# Sound_Recorder_IoT_updated.net
KiCad netlist of a schematic drawn in EasyEDA Pro
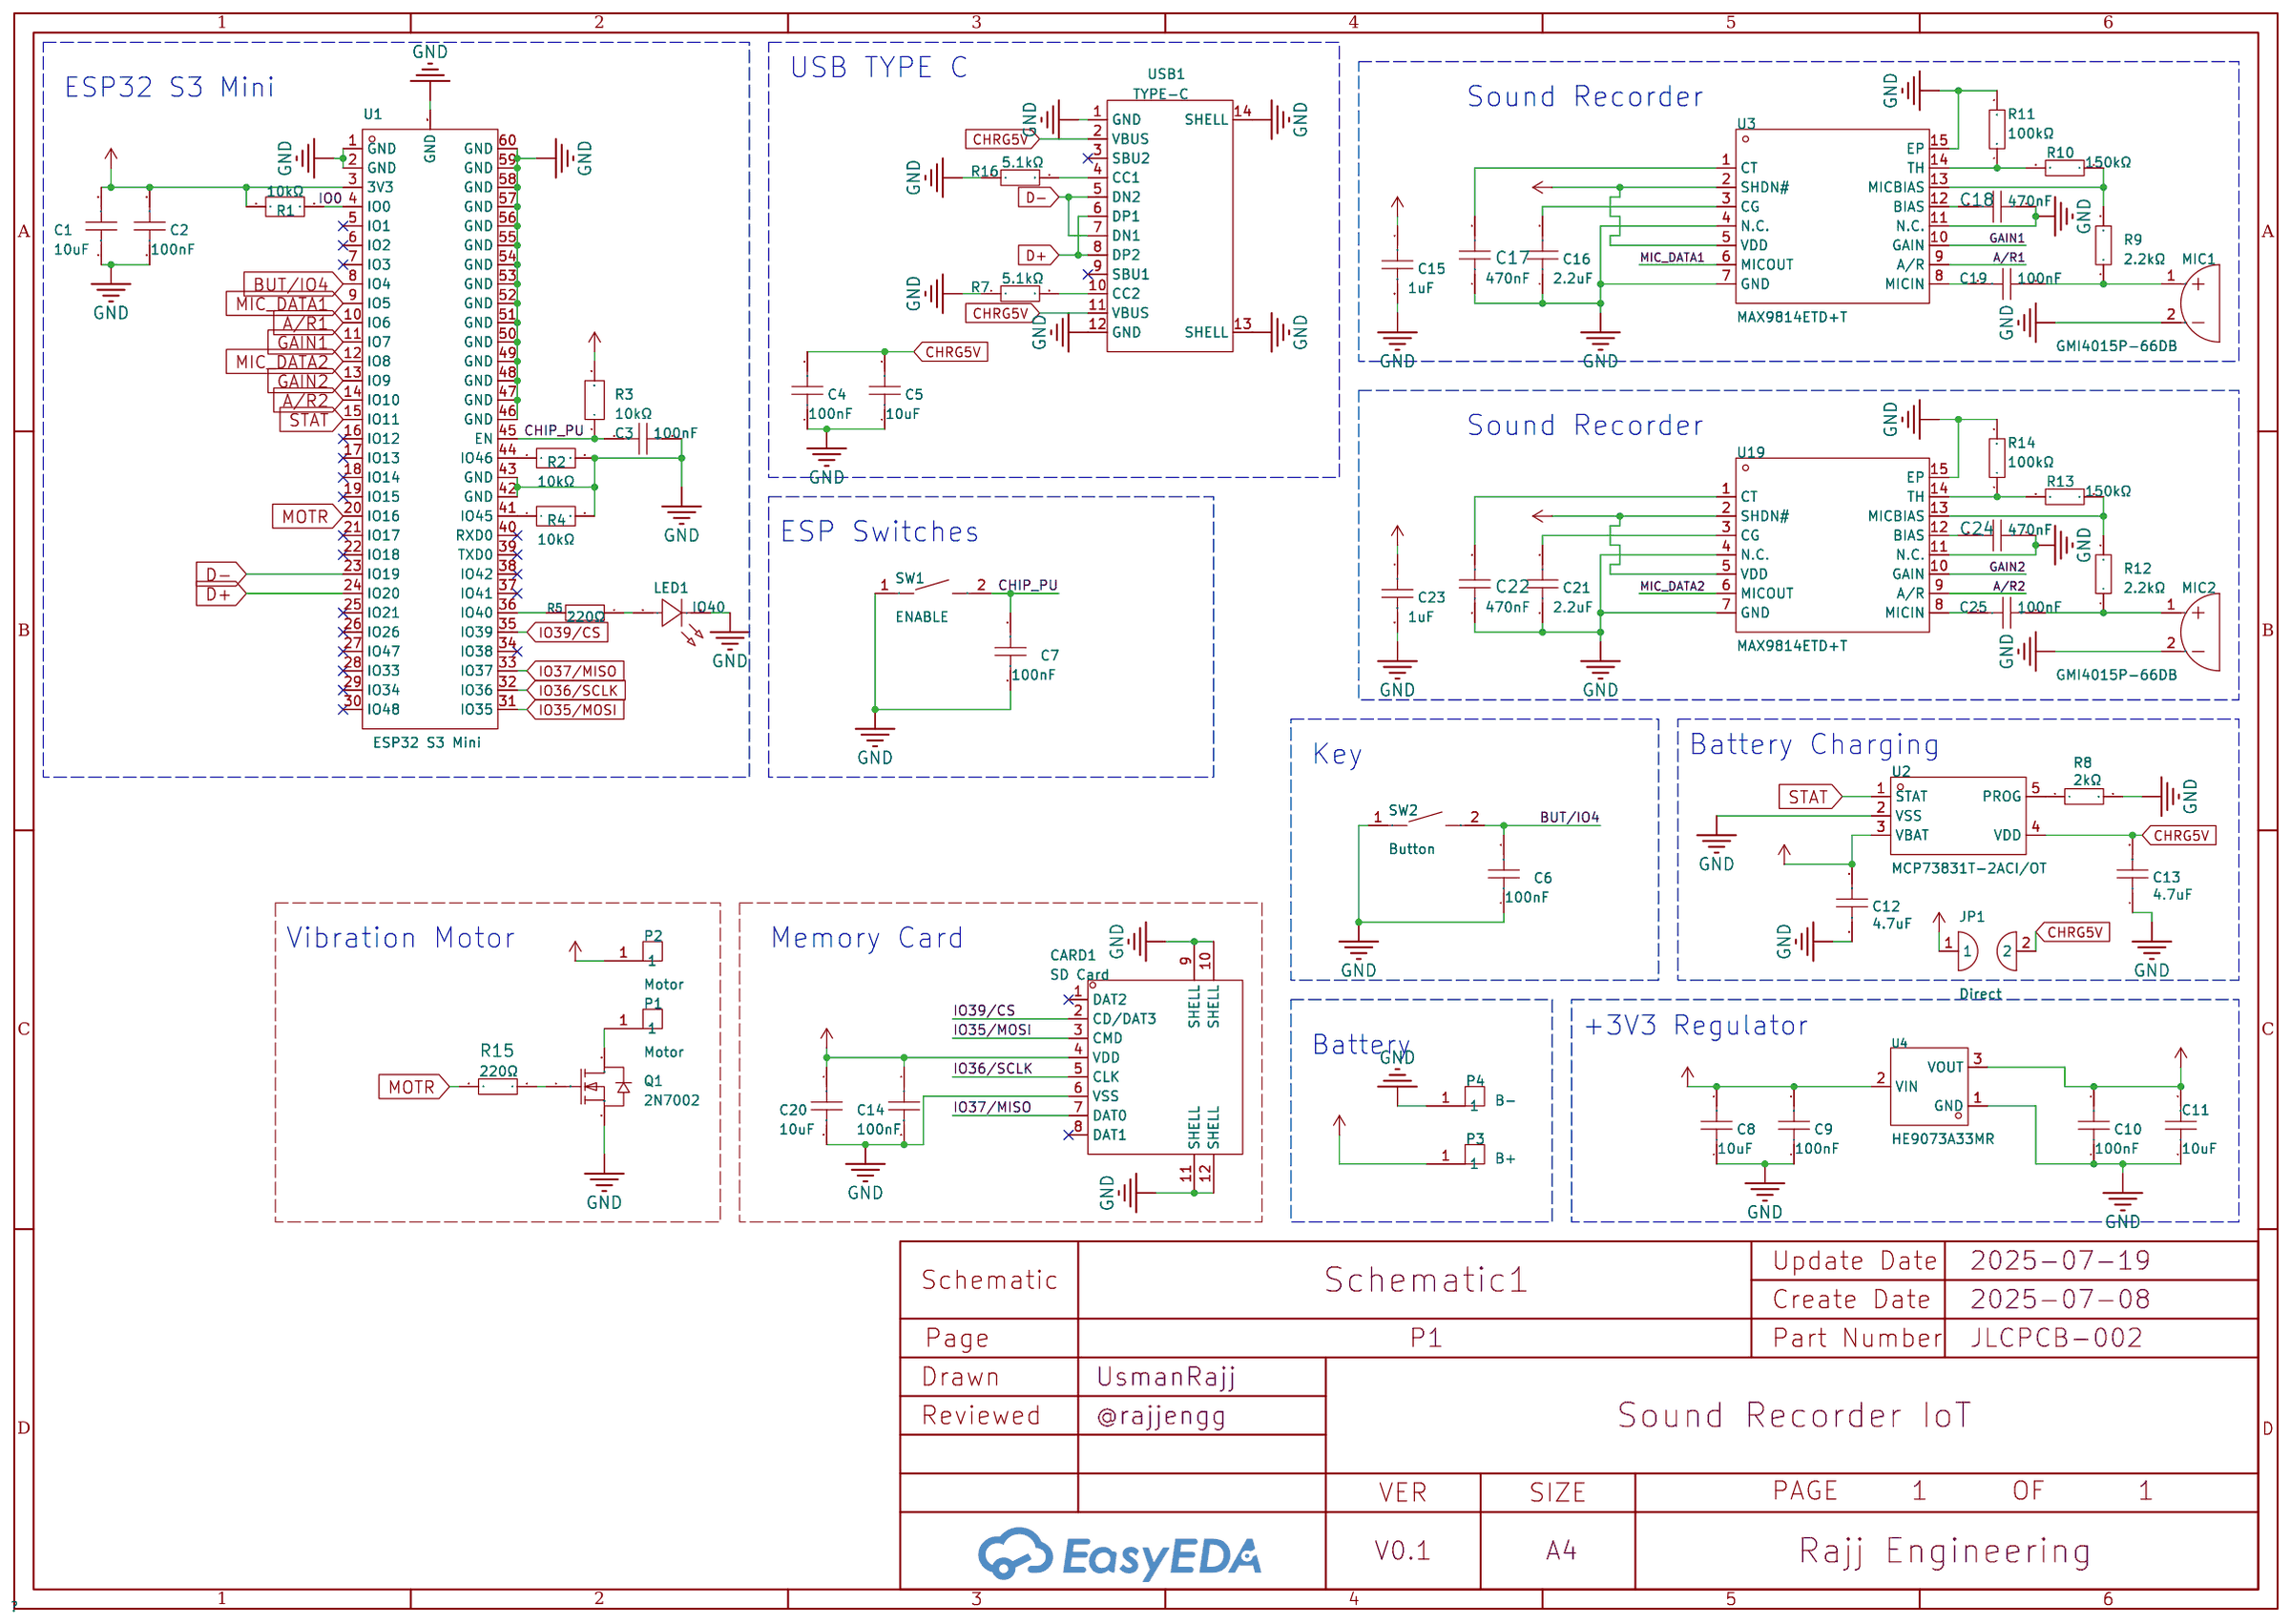
[diagram p0: schematic sheet]

(export (version "E")
  (design (tool "Eeschema 10.0.6"))
  (components
    (comp (ref "C1")
      (value "10uF")
      (footprint "easyedapro:C0402")
      (fields
        (field (name "Manufacturer Part") "CL05A106MP5NUNC")
        (field (name "Manufacturer") "SAMSUNG(三星)")
      )
      (libsource (lib "easyedapro") (part "CL05A106MP5NUNC_C315248"))
    )
    (comp (ref "C2")
      (value "100nF")
      (footprint "easyedapro:C0201")
      (description "Capacitance:100nF Tolerance:±10% Tolerance:±10% Voltage Rating:10V Temperature Coefficient:X5R")
      (fields (field (name "Manufacturer Part") "0201X104K100NT") (field (name "Manufacturer") "FH(风华)"))
      (libsource (lib "easyedapro") (part "0201X104K100NT"))
    )
    (comp (ref "C3")
      (value "100nF")
      (footprint "easyedapro:C0201")
      (description "Capacitance:100nF Tolerance:±10% Tolerance:±10% Voltage Rating:10V Temperature Coefficient:X5R")
      (fields (field (name "Manufacturer Part") "0201X104K100NT") (field (name "Manufacturer") "FH(风华)"))
      (libsource (lib "easyedapro") (part "0201X104K100NT"))
    )
    (comp (ref "C4")
      (value "100nF")
      (footprint "easyedapro:C0201")
      (description "Capacitance:100nF Tolerance:±10% Tolerance:±10% Voltage Rating:10V Temperature Coefficient:X5R")
      (fields (field (name "Manufacturer Part") "0201X104K100NT") (field (name "Manufacturer") "FH(风华)"))
      (libsource (lib "easyedapro") (part "0201X104K100NT"))
    )
    (comp (ref "C5")
      (value "10uF")
      (footprint "easyedapro:C0402")
      (fields
        (field (name "Manufacturer Part") "CL05A106MP5NUNC")
        (field (name "Manufacturer") "SAMSUNG(三星)")
      )
      (libsource (lib "easyedapro") (part "CL05A106MP5NUNC_C315248"))
    )
    (comp (ref "C6")
      (value "100nF")
      (footprint "easyedapro:C0201")
      (description "Capacitance:100nF Tolerance:±10% Tolerance:±10% Voltage Rating:10V Temperature Coefficient:X5R")
      (fields (field (name "Manufacturer Part") "0201X104K100NT") (field (name "Manufacturer") "FH(风华)"))
      (libsource (lib "easyedapro") (part "0201X104K100NT"))
    )
    (comp (ref "C7")
      (value "100nF")
      (footprint "easyedapro:C0201")
      (description "Capacitance:100nF Tolerance:±10% Tolerance:±10% Voltage Rating:10V Temperature Coefficient:X5R")
      (fields (field (name "Manufacturer Part") "0201X104K100NT") (field (name "Manufacturer") "FH(风华)"))
      (libsource (lib "easyedapro") (part "0201X104K100NT"))
    )
    (comp (ref "C8")
      (value "10uF")
      (footprint "easyedapro:C0402")
      (fields
        (field (name "Manufacturer Part") "CL05A106MP5NUNC")
        (field (name "Manufacturer") "SAMSUNG(三星)")
      )
      (libsource (lib "easyedapro") (part "CL05A106MP5NUNC_C315248"))
    )
    (comp (ref "C9")
      (value "100nF")
      (footprint "easyedapro:C0201")
      (description "Capacitance:100nF Tolerance:±10% Tolerance:±10% Voltage Rating:10V Temperature Coefficient:X5R")
      (fields (field (name "Manufacturer Part") "0201X104K100NT") (field (name "Manufacturer") "FH(风华)"))
      (libsource (lib "easyedapro") (part "0201X104K100NT"))
    )
    (comp (ref "C10")
      (value "100nF")
      (footprint "easyedapro:C0201")
      (description "Capacitance:100nF Tolerance:±10% Tolerance:±10% Voltage Rating:10V Temperature Coefficient:X5R")
      (fields (field (name "Manufacturer Part") "0201X104K100NT") (field (name "Manufacturer") "FH(风华)"))
      (libsource (lib "easyedapro") (part "0201X104K100NT"))
    )
    (comp (ref "C11")
      (value "10uF")
      (footprint "easyedapro:C0402")
      (fields
        (field (name "Manufacturer Part") "CL05A106MP5NUNC")
        (field (name "Manufacturer") "SAMSUNG(三星)")
      )
      (libsource (lib "easyedapro") (part "CL05A106MP5NUNC_C315248"))
    )
    (comp (ref "C12")
      (value "4.7uF")
      (footprint "easyedapro:C0402")
      (fields
        (field (name "Manufacturer Part") "CL05A475KP5NRNC")
        (field (name "Manufacturer") "SAMSUNG(三星)")
      )
      (libsource (lib "easyedapro") (part "4.7uF"))
    )
    (comp (ref "C13")
      (value "4.7uF")
      (footprint "easyedapro:C0402")
      (fields
        (field (name "Manufacturer Part") "CL05A475KP5NRNC")
        (field (name "Manufacturer") "SAMSUNG(三星)")
      )
      (libsource (lib "easyedapro") (part "4.7uF"))
    )
    (comp (ref "C14")
      (value "100nF")
      (footprint "easyedapro:C0201")
      (description "Capacitance:100nF Tolerance:±10% Tolerance:±10% Voltage Rating:10V Temperature Coefficient:X5R")
      (fields (field (name "Manufacturer Part") "0201X104K100NT") (field (name "Manufacturer") "FH(风华)"))
      (libsource (lib "easyedapro") (part "0201X104K100NT"))
    )
    (comp (ref "C15")
      (value "1uF")
      (footprint "easyedapro:C0201")
      (fields
        (field (name "Manufacturer Part") "CL03A105MP3NSNC")
        (field (name "Manufacturer") "SAMSUNG(三星)")
      )
      (libsource (lib "easyedapro") (part "CL03A105MP3NSNC"))
    )
    (comp (ref "C16")
      (value "2.2uF")
      (footprint "easyedapro:C0201")
      (description "Capacitance:2.2uF Tolerance:±20% Tolerance:±20% Voltage Rating:6.3V Temperature Coefficient:X5R")
      (fields (field (name "Manufacturer Part") "0201X225M6R3NT") (field (name "Manufacturer") "FH(风华)"))
      (libsource (lib "easyedapro") (part "0201X225M6R3NT"))
    )
    (comp (ref "C17")
      (value "470nF")
      (footprint "easyedapro:C0201")
      (fields
        (field (name "Manufacturer Part") "GRM033R60J474KE90D")
        (field (name "Manufacturer") "muRata(村田)")
      )
      (libsource (lib "easyedapro") (part "GRM033R60J474KE90D"))
    )
    (comp (ref "C18")
      (value "470nF")
      (footprint "easyedapro:C0201")
      (fields
        (field (name "Manufacturer Part") "GRM033R60J474KE90D")
        (field (name "Manufacturer") "muRata(村田)")
      )
      (libsource (lib "easyedapro") (part "GRM033R60J474KE90D"))
    )
    (comp (ref "C19")
      (value "100nF")
      (footprint "easyedapro:C0201")
      (description "Capacitance:100nF Tolerance:±10% Tolerance:±10% Voltage Rating:10V Temperature Coefficient:X5R")
      (fields (field (name "Manufacturer Part") "0201X104K100NT") (field (name "Manufacturer") "FH(风华)"))
      (libsource (lib "easyedapro") (part "0201X104K100NT"))
    )
    (comp (ref "C20")
      (value "10uF")
      (footprint "easyedapro:C0402")
      (fields
        (field (name "Manufacturer Part") "CL05A106MP5NUNC")
        (field (name "Manufacturer") "SAMSUNG(三星)")
      )
      (libsource (lib "easyedapro") (part "CL05A106MP5NUNC_C315248"))
    )
    (comp (ref "C21")
      (value "2.2uF")
      (footprint "easyedapro:C0201")
      (description "Capacitance:2.2uF Tolerance:±20% Tolerance:±20% Voltage Rating:6.3V Temperature Coefficient:X5R")
      (fields (field (name "Manufacturer Part") "0201X225M6R3NT") (field (name "Manufacturer") "FH(风华)"))
      (libsource (lib "easyedapro") (part "0201X225M6R3NT"))
    )
    (comp (ref "C22")
      (value "470nF")
      (footprint "easyedapro:C0201")
      (fields
        (field (name "Manufacturer Part") "GRM033R60J474KE90D")
        (field (name "Manufacturer") "muRata(村田)")
      )
      (libsource (lib "easyedapro") (part "GRM033R60J474KE90D"))
    )
    (comp (ref "C23")
      (value "1uF")
      (footprint "easyedapro:C0201")
      (fields
        (field (name "Manufacturer Part") "CL03A105MP3NSNC")
        (field (name "Manufacturer") "SAMSUNG(三星)")
      )
      (libsource (lib "easyedapro") (part "CL03A105MP3NSNC"))
    )
    (comp (ref "C24")
      (value "470nF")
      (footprint "easyedapro:C0201")
      (fields
        (field (name "Manufacturer Part") "GRM033R60J474KE90D")
        (field (name "Manufacturer") "muRata(村田)")
      )
      (libsource (lib "easyedapro") (part "GRM033R60J474KE90D"))
    )
    (comp (ref "C25")
      (value "100nF")
      (footprint "easyedapro:C0201")
      (description "Capacitance:100nF Tolerance:±10% Tolerance:±10% Voltage Rating:10V Temperature Coefficient:X5R")
      (fields (field (name "Manufacturer Part") "0201X104K100NT") (field (name "Manufacturer") "FH(风华)"))
      (libsource (lib "easyedapro") (part "0201X104K100NT"))
    )
    (comp (ref "CARD1")
      (value "SD Card")
      (footprint "easyedapro:TF-SMD_TF-102-15")
      (fields (field (name "Manufacturer Part") "TF-102-15") (field (name "Manufacturer") "XUNPU(讯普)"))
      (libsource (lib "easyedapro") (part "TF-102-15"))
    )
    (comp (ref "JP1")
      (value "Direct")
      (footprint "easyedapro:jumper pad")
      (libsource (lib "easyedapro") (part "Jumper Pad"))
    )
    (comp (ref "LED1")
      (value "IO40")
      (footprint "easyedapro:LED0603-RD_BLUE")
      (fields
        (field (name "Manufacturer Part") "XL-1608UBC-04")
        (field (name "Manufacturer") "XINGLIGHT(成兴光)")
      )
      (libsource (lib "easyedapro") (part "XL-1608UBC-04"))
    )
    (comp (ref "MIC1")
      (value "GMI4015P-66DB")
      (footprint "easyedapro:MIC-TH_BD4.0-P1.4-D0.4-L-FD")
      (fields (field (name "Manufacturer") "INGHAi(赢海)"))
      (libsource (lib "easyedapro") (part "GMI4015P-66DB"))
    )
    (comp (ref "MIC2")
      (value "GMI4015P-66DB")
      (footprint "easyedapro:MIC-TH_BD4.0-P1.4-D0.4-L-FD")
      (fields (field (name "Manufacturer") "INGHAi(赢海)"))
      (libsource (lib "easyedapro") (part "GMI4015P-66DB"))
    )
    (comp (ref "P1") (value "Motor") (libsource (lib "easyedapro") (part "SMD 1.5X2 PAD")))
    (comp (ref "P2") (value "Motor") (libsource (lib "easyedapro") (part "SMD 1.5X2 PAD")))
    (comp (ref "P3") (value "B+") (libsource (lib "easyedapro") (part "SMD 1.5X2 PAD")))
    (comp (ref "P4") (value "B-") (libsource (lib "easyedapro") (part "SMD 1.5X2 PAD")))
    (comp (ref "Q1")
      (value "2N7002")
      (footprint "easyedapro:SOT-23-3_L2.9-W1.3-P1.90-LS2.4-BR")
      (fields (field (name "Manufacturer") "CJ(江苏长电/长晶)"))
      (libsource (lib "easyedapro") (part "2N7002"))
    )
    (comp (ref "R1")
      (value "10kΩ")
      (footprint "easyedapro:R0201")
      (fields
        (field (name "Manufacturer Part") "0201WMF1002TEE")
        (field (name "Manufacturer") "UNI-ROYAL(厚声)")
      )
      (libsource (lib "easyedapro") (part "0201WMF1002TEE"))
    )
    (comp (ref "R2")
      (value "10kΩ")
      (footprint "easyedapro:R0201")
      (fields
        (field (name "Manufacturer Part") "0201WMF1002TEE")
        (field (name "Manufacturer") "UNI-ROYAL(厚声)")
      )
      (libsource (lib "easyedapro") (part "0201WMF1002TEE"))
    )
    (comp (ref "R3")
      (value "10kΩ")
      (footprint "easyedapro:R0201")
      (fields
        (field (name "Manufacturer Part") "0201WMF1002TEE")
        (field (name "Manufacturer") "UNI-ROYAL(厚声)")
      )
      (libsource (lib "easyedapro") (part "0201WMF1002TEE"))
    )
    (comp (ref "R4")
      (value "10kΩ")
      (footprint "easyedapro:R0201")
      (fields
        (field (name "Manufacturer Part") "0201WMF1002TEE")
        (field (name "Manufacturer") "UNI-ROYAL(厚声)")
      )
      (libsource (lib "easyedapro") (part "0201WMF1002TEE"))
    )
    (comp (ref "R5")
      (value "220Ω")
      (footprint "easyedapro:R0402")
      (fields
        (field (name "Manufacturer Part") "0402WGF2200TCE")
        (field (name "Manufacturer") "UNI-ROYAL(厚声)")
      )
      (libsource (lib "easyedapro") (part "0402WGF2200TCE"))
    )
    (comp (ref "R7")
      (value "5.1kΩ")
      (footprint "easyedapro:R0402")
      (fields
        (field (name "Manufacturer Part") "0402WGF5101TCE")
        (field (name "Manufacturer") "UNI-ROYAL(厚声)")
      )
      (libsource (lib "easyedapro") (part "5.1kΩ"))
    )
    (comp (ref "R8")
      (value "2kΩ")
      (footprint "easyedapro:R0402")
      (fields
        (field (name "Manufacturer Part") "0402WGF2001TCE")
        (field (name "Manufacturer") "UNI-ROYAL(厚声)")
      )
      (libsource (lib "easyedapro") (part "2kΩ"))
    )
    (comp (ref "R9")
      (value "2.2kΩ")
      (footprint "easyedapro:R0201")
      (fields (field (name "Manufacturer Part") "RC0201FR-072K2L") (field (name "Manufacturer") "YAGEO(国巨)"))
      (libsource (lib "easyedapro") (part "RC0201FR-072K2L"))
    )
    (comp (ref "R10")
      (value "150kΩ")
      (footprint "easyedapro:R0201")
      (fields (field (name "Manufacturer Part") "RC0201FR-07150KL") (field (name "Manufacturer") "YAGEO(国巨)"))
      (libsource (lib "easyedapro") (part "RC0201FR-07150KL"))
    )
    (comp (ref "R11")
      (value "100kΩ")
      (footprint "easyedapro:R0201")
      (fields (field (name "Manufacturer Part") "RC0201FR-07100KL") (field (name "Manufacturer") "YAGEO(国巨)"))
      (libsource (lib "easyedapro") (part "RC0201FR-07100KL"))
    )
    (comp (ref "R12")
      (value "2.2kΩ")
      (footprint "easyedapro:R0201")
      (fields (field (name "Manufacturer Part") "RC0201FR-072K2L") (field (name "Manufacturer") "YAGEO(国巨)"))
      (libsource (lib "easyedapro") (part "RC0201FR-072K2L"))
    )
    (comp (ref "R13")
      (value "150kΩ")
      (footprint "easyedapro:R0201")
      (fields (field (name "Manufacturer Part") "RC0201FR-07150KL") (field (name "Manufacturer") "YAGEO(国巨)"))
      (libsource (lib "easyedapro") (part "RC0201FR-07150KL"))
    )
    (comp (ref "R14")
      (value "100kΩ")
      (footprint "easyedapro:R0201")
      (fields (field (name "Manufacturer Part") "RC0201FR-07100KL") (field (name "Manufacturer") "YAGEO(国巨)"))
      (libsource (lib "easyedapro") (part "RC0201FR-07100KL"))
    )
    (comp (ref "R15")
      (value "220Ω")
      (footprint "easyedapro:R0402")
      (fields
        (field (name "Manufacturer Part") "0402WGF2200TCE")
        (field (name "Manufacturer") "UNI-ROYAL(厚声)")
      )
      (libsource (lib "easyedapro") (part "0402WGF2200TCE"))
    )
    (comp (ref "R16")
      (value "5.1kΩ")
      (footprint "easyedapro:R0402")
      (fields
        (field (name "Manufacturer Part") "0402WGF5101TCE")
        (field (name "Manufacturer") "UNI-ROYAL(厚声)")
      )
      (libsource (lib "easyedapro") (part "5.1kΩ"))
    )
    (comp (ref "SW1")
      (value "ENABLE")
      (footprint "easyedapro:SW-SMD_L3.9-W3.0-P4.45")
      (fields (field (name "Manufacturer Part") "TS-1088-AR02016") (field (name "Manufacturer") "XUNPU(讯普)"))
      (libsource (lib "easyedapro") (part "TS-1088-AR02016"))
    )
    (comp (ref "SW2")
      (value "Button")
      (footprint "easyedapro:SW-SMD_L3.9-W3.0-P4.45")
      (fields (field (name "Manufacturer Part") "TS-1088-AR02016") (field (name "Manufacturer") "XUNPU(讯普)"))
      (libsource (lib "easyedapro") (part "TS-1088-AR02016"))
    )
    (comp (ref "U1")
      (value "ESP32 S3 Mini")
      (footprint "easyedapro:BULETM-SMD_ESP32-S3-MINI-1-N8")
      (fields
        (field (name "Manufacturer Part") "ESP32-S3-MINI-1-N8")
        (field (name "Manufacturer") "ESPRESSIF(乐鑫)")
      )
      (libsource (lib "easyedapro") (part "ESP32-S3-MINI-1-N8"))
    )
    (comp (ref "U2")
      (value "MCP73831T-2ACI/OT")
      (footprint "easyedapro:SOT-23-5_L3.0-W1.7-P0.95-LS2.8-BL")
      (fields (field (name "Manufacturer") "MICROCHIP(美国微芯)"))
      (libsource (lib "easyedapro") (part "MCP73831T-2ACI/OT"))
    )
    (comp (ref "U3")
      (value "MAX9814ETD+T")
      (footprint "easyedapro:TDFN-14_L3.0-W3.0-P0.40-BL-EP")
      (fields (field (name "Manufacturer") "ADI(亚德诺)/MAXIM(美信)"))
      (libsource (lib "easyedapro") (part "MAX9814ETD+T"))
    )
    (comp (ref "U4")
      (value "HE9073A33MR")
      (footprint "easyedapro:SOT-23-3_L2.9-W1.6-P1.90-LS2.8-BR-CW")
      (fields (field (name "Manufacturer") "HEERMICR(赫尔半导体)"))
      (libsource (lib "easyedapro") (part "HE9073A33MR"))
    )
    (comp (ref "U19")
      (value "MAX9814ETD+T")
      (footprint "easyedapro:TDFN-14_L3.0-W3.0-P0.40-BL-EP")
      (fields (field (name "Manufacturer") "ADI(亚德诺)/MAXIM(美信)"))
      (libsource (lib "easyedapro") (part "MAX9814ETD+T"))
    )
    (comp (ref "USB1")
      (value "TYPE-C")
      (footprint "easyedapro:USB-C-SMD_TYPE-C-6PIN-2MD-073")
      (fields
        (field (name "Manufacturer Part") "TYPE-C 16PIN 2MD(073)")
        (field (name "Manufacturer") "SHOU HAN(首韩)")
      )
      (libsource (lib "easyedapro") (part "TYPE-C"))
    )
  )
  (nets
    (net (code "1") (name "/CHIP_PU") (class "Default")
      (node (ref "C3") (pin "2") (pinfunction "2_2") (pintype "unspecified"))
      (node (ref "C7") (pin "2") (pinfunction "2_2") (pintype "unspecified"))
      (node (ref "R3") (pin "1") (pinfunction "1_1") (pintype "unspecified"))
      (node (ref "SW1") (pin "2") (pinfunction "2_2") (pintype "unspecified"))
      (node (ref "U1") (pin "45") (pinfunction "EN_45") (pintype "unspecified"))
    )
    (net (code "2") (name "/IO0") (class "Default")
      (node (ref "R1") (pin "2") (pinfunction "2_2") (pintype "unspecified"))
      (node (ref "U1") (pin "4") (pinfunction "IO0_4") (pintype "unspecified"))
    )
    (net (code "3") (name "A{slash}R1") (class "Default")
      (node (ref "U1") (pin "10") (pinfunction "IO6_10") (pintype "unspecified"))
      (node (ref "U3") (pin "9") (pinfunction "A/R_9") (pintype "unspecified"))
    )
    (net (code "4") (name "A{slash}R2") (class "Default")
      (node (ref "U1") (pin "14") (pinfunction "IO10_14") (pintype "unspecified"))
      (node (ref "U19") (pin "9") (pinfunction "A/R_9") (pintype "unspecified"))
    )
    (net (code "5") (name "BUT{slash}IO4") (class "Default")
      (node (ref "C6") (pin "2") (pinfunction "2_2") (pintype "unspecified"))
      (node (ref "SW2") (pin "2") (pinfunction "2_2") (pintype "unspecified"))
      (node (ref "U1") (pin "8") (pinfunction "IO4_8") (pintype "unspecified"))
    )
    (net (code "6") (name "CHRG5V") (class "Default")
      (node (ref "C13") (pin "2") (pinfunction "2_2") (pintype "unspecified"))
      (node (ref "C4") (pin "2") (pinfunction "2_2") (pintype "unspecified"))
      (node (ref "C5") (pin "2") (pinfunction "2_2") (pintype "unspecified"))
      (node (ref "JP1") (pin "2") (pinfunction "2_2") (pintype "input"))
      (node (ref "U2") (pin "4") (pinfunction "VDD_4") (pintype "unspecified"))
      (node (ref "USB1") (pin "11") (pinfunction "VBUS_11") (pintype "unspecified"))
      (node (ref "USB1") (pin "2") (pinfunction "VBUS_2") (pintype "unspecified"))
    )
    (net (code "7") (name "D+") (class "Default")
      (node (ref "U1") (pin "24") (pinfunction "IO20_24") (pintype "unspecified"))
      (node (ref "USB1") (pin "6") (pinfunction "DP1_6") (pintype "unspecified"))
      (node (ref "USB1") (pin "8") (pinfunction "DP2_8") (pintype "unspecified"))
    )
    (net (code "8") (name "D-") (class "Default")
      (node (ref "U1") (pin "23") (pinfunction "IO19_23") (pintype "unspecified"))
      (node (ref "USB1") (pin "5") (pinfunction "DN2_5") (pintype "unspecified"))
      (node (ref "USB1") (pin "7") (pinfunction "DN1_7") (pintype "unspecified"))
    )
    (net (code "9") (name "GAIN1") (class "Default")
      (node (ref "U1") (pin "11") (pinfunction "IO7_11") (pintype "unspecified"))
      (node (ref "U3") (pin "10") (pinfunction "GAIN_10") (pintype "unspecified"))
    )
    (net (code "10") (name "GAIN2") (class "Default")
      (node (ref "U1") (pin "13") (pinfunction "IO9_13") (pintype "unspecified"))
      (node (ref "U19") (pin "10") (pinfunction "GAIN_10") (pintype "unspecified"))
    )
    (net (code "11") (name "GND") (class "Default")
      (node (ref "C1") (pin "1") (pinfunction "1_1") (pintype "unspecified"))
      (node (ref "C10") (pin "1") (pinfunction "1_1") (pintype "unspecified"))
      (node (ref "C11") (pin "1") (pinfunction "1_1") (pintype "unspecified"))
      (node (ref "C12") (pin "1") (pinfunction "1_1") (pintype "unspecified"))
      (node (ref "C13") (pin "1") (pinfunction "1_1") (pintype "unspecified"))
      (node (ref "C14") (pin "2") (pinfunction "2_2") (pintype "unspecified"))
      (node (ref "C15") (pin "2") (pinfunction "2_2") (pintype "input"))
      (node (ref "C16") (pin "1") (pinfunction "1_1") (pintype "unspecified"))
      (node (ref "C17") (pin "1") (pinfunction "1_1") (pintype "input"))
      (node (ref "C18") (pin "1") (pinfunction "1_1") (pintype "input"))
      (node (ref "C2") (pin "1") (pinfunction "1_1") (pintype "unspecified"))
      (node (ref "C20") (pin "2") (pinfunction "2_2") (pintype "unspecified"))
      (node (ref "C21") (pin "1") (pinfunction "1_1") (pintype "unspecified"))
      (node (ref "C22") (pin "1") (pinfunction "1_1") (pintype "input"))
      (node (ref "C23") (pin "2") (pinfunction "2_2") (pintype "input"))
      (node (ref "C24") (pin "1") (pinfunction "1_1") (pintype "input"))
      (node (ref "C3") (pin "1") (pinfunction "1_1") (pintype "unspecified"))
      (node (ref "C4") (pin "1") (pinfunction "1_1") (pintype "unspecified"))
      (node (ref "C5") (pin "1") (pinfunction "1_1") (pintype "unspecified"))
      (node (ref "C6") (pin "1") (pinfunction "1_1") (pintype "unspecified"))
      (node (ref "C7") (pin "1") (pinfunction "1_1") (pintype "unspecified"))
      (node (ref "C8") (pin "1") (pinfunction "1_1") (pintype "unspecified"))
      (node (ref "C9") (pin "1") (pinfunction "1_1") (pintype "unspecified"))
      (node (ref "CARD1") (pin "10") (pinfunction "SHELL_10") (pintype "unspecified"))
      (node (ref "CARD1") (pin "11") (pinfunction "SHELL_11") (pintype "unspecified"))
      (node (ref "CARD1") (pin "12") (pinfunction "SHELL_12") (pintype "unspecified"))
      (node (ref "CARD1") (pin "6") (pinfunction "VSS_6") (pintype "unspecified"))
      (node (ref "CARD1") (pin "9") (pinfunction "SHELL_9") (pintype "unspecified"))
      (node (ref "LED1") (pin "1") (pinfunction "K_1") (pintype "unspecified"))
      (node (ref "MIC1") (pin "2") (pinfunction "2_2") (pintype "unspecified"))
      (node (ref "MIC2") (pin "2") (pinfunction "2_2") (pintype "unspecified"))
      (node (ref "P4") (pin "1") (pinfunction "1_1") (pintype "input"))
      (node (ref "Q1") (pin "2") (pinfunction "S_2") (pintype "unspecified"))
      (node (ref "R11") (pin "2") (pinfunction "2_2") (pintype "unspecified"))
      (node (ref "R14") (pin "2") (pinfunction "2_2") (pintype "unspecified"))
      (node (ref "R16") (pin "1") (pinfunction "1_1") (pintype "input"))
      (node (ref "R2") (pin "2") (pinfunction "2_2") (pintype "unspecified"))
      (node (ref "R4") (pin "2") (pinfunction "2_2") (pintype "unspecified"))
      (node (ref "R7") (pin "1") (pinfunction "1_1") (pintype "input"))
      (node (ref "R8") (pin "2") (pinfunction "2_2") (pintype "input"))
      (node (ref "SW1") (pin "1") (pinfunction "1_1") (pintype "unspecified"))
      (node (ref "SW2") (pin "1") (pinfunction "1_1") (pintype "unspecified"))
      (node (ref "U1") (pin "1") (pinfunction "GND_1") (pintype "unspecified"))
      (node (ref "U1") (pin "2") (pinfunction "GND_2") (pintype "unspecified"))
      (node (ref "U1") (pin "42") (pinfunction "GND_42") (pintype "unspecified"))
      (node (ref "U1") (pin "43") (pinfunction "GND_43") (pintype "unspecified"))
      (node (ref "U1") (pin "46") (pinfunction "GND_46") (pintype "unspecified"))
      (node (ref "U1") (pin "47") (pinfunction "GND_47") (pintype "unspecified"))
      (node (ref "U1") (pin "48") (pinfunction "GND_48") (pintype "unspecified"))
      (node (ref "U1") (pin "49") (pinfunction "GND_49") (pintype "unspecified"))
      (node (ref "U1") (pin "50") (pinfunction "GND_50") (pintype "unspecified"))
      (node (ref "U1") (pin "51") (pinfunction "GND_51") (pintype "unspecified"))
      (node (ref "U1") (pin "52") (pinfunction "GND_52") (pintype "unspecified"))
      (node (ref "U1") (pin "53") (pinfunction "GND_53") (pintype "unspecified"))
      (node (ref "U1") (pin "54") (pinfunction "GND_54") (pintype "unspecified"))
      (node (ref "U1") (pin "55") (pinfunction "GND_55") (pintype "unspecified"))
      (node (ref "U1") (pin "56") (pinfunction "GND_56") (pintype "unspecified"))
      (node (ref "U1") (pin "57") (pinfunction "GND_57") (pintype "unspecified"))
      (node (ref "U1") (pin "58") (pinfunction "GND_58") (pintype "unspecified"))
      (node (ref "U1") (pin "59") (pinfunction "GND_59") (pintype "unspecified"))
      (node (ref "U1") (pin "60") (pinfunction "GND_60") (pintype "unspecified"))
      (node (ref "U1") (pin "GND") (pinfunction "GND_GND") (pintype "unspecified"))
      (node (ref "U19") (pin "11") (pinfunction "N.C._11") (pintype "unspecified"))
      (node (ref "U19") (pin "15") (pinfunction "EP_15") (pintype "unspecified"))
      (node (ref "U19") (pin "4") (pinfunction "N.C._4") (pintype "unspecified"))
      (node (ref "U19") (pin "7") (pinfunction "GND_7") (pintype "unspecified"))
      (node (ref "U2") (pin "2") (pinfunction "VSS_2") (pintype "unspecified"))
      (node (ref "U3") (pin "11") (pinfunction "N.C._11") (pintype "unspecified"))
      (node (ref "U3") (pin "15") (pinfunction "EP_15") (pintype "unspecified"))
      (node (ref "U3") (pin "4") (pinfunction "N.C._4") (pintype "unspecified"))
      (node (ref "U3") (pin "7") (pinfunction "GND_7") (pintype "unspecified"))
      (node (ref "U4") (pin "1") (pinfunction "GND_1") (pintype "input"))
      (node (ref "USB1") (pin "1") (pinfunction "GND_1") (pintype "unspecified"))
      (node (ref "USB1") (pin "12") (pinfunction "GND_12") (pintype "unspecified"))
      (node (ref "USB1") (pin "13") (pinfunction "SHELL_13") (pintype "unspecified"))
      (node (ref "USB1") (pin "14") (pinfunction "SHELL_14") (pintype "unspecified"))
    )
    (net (code "12") (name "IO35{slash}MOSI") (class "Default")
      (node (ref "CARD1") (pin "3") (pinfunction "CMD_3") (pintype "unspecified"))
      (node (ref "U1") (pin "31") (pinfunction "IO35_31") (pintype "unspecified"))
    )
    (net (code "13") (name "IO36{slash}SCLK") (class "Default")
      (node (ref "CARD1") (pin "5") (pinfunction "CLK_5") (pintype "unspecified"))
      (node (ref "U1") (pin "32") (pinfunction "IO36_32") (pintype "unspecified"))
    )
    (net (code "14") (name "IO37{slash}MISO") (class "Default")
      (node (ref "CARD1") (pin "7") (pinfunction "DAT0_7") (pintype "unspecified"))
      (node (ref "U1") (pin "33") (pinfunction "IO37_33") (pintype "unspecified"))
    )
    (net (code "15") (name "IO39{slash}CS") (class "Default")
      (node (ref "CARD1") (pin "2") (pinfunction "CD/DAT3_2") (pintype "unspecified"))
      (node (ref "U1") (pin "35") (pinfunction "IO39_35") (pintype "unspecified"))
    )
    (net (code "16") (name "MIC_DATA1") (class "Default")
      (node (ref "U1") (pin "9") (pinfunction "IO5_9") (pintype "unspecified"))
      (node (ref "U3") (pin "6") (pinfunction "MICOUT_6") (pintype "unspecified"))
    )
    (net (code "17") (name "MIC_DATA2") (class "Default")
      (node (ref "U1") (pin "12") (pinfunction "IO8_12") (pintype "unspecified"))
      (node (ref "U19") (pin "6") (pinfunction "MICOUT_6") (pintype "unspecified"))
    )
    (net (code "18") (name "MOTR") (class "Default")
      (node (ref "R15") (pin "2") (pinfunction "2_2") (pintype "input"))
      (node (ref "U1") (pin "20") (pinfunction "IO16_20") (pintype "unspecified"))
    )
    (net (code "19") (name "Net-(C19-Pad1)") (class "Default")
      (node (ref "C19") (pin "1") (pinfunction "1_1") (pintype "unspecified"))
      (node (ref "MIC1") (pin "1") (pinfunction "1_1") (pintype "unspecified"))
      (node (ref "R9") (pin "1") (pinfunction "1_1") (pintype "input"))
    )
    (net (code "20") (name "Net-(C25-Pad1)") (class "Default")
      (node (ref "C25") (pin "1") (pinfunction "1_1") (pintype "unspecified"))
      (node (ref "MIC2") (pin "1") (pinfunction "1_1") (pintype "unspecified"))
      (node (ref "R12") (pin "1") (pinfunction "1_1") (pintype "input"))
    )
    (net (code "21") (name "Net-(LED1-A)") (class "Default")
      (node (ref "LED1") (pin "2") (pinfunction "A_2") (pintype "unspecified"))
      (node (ref "R5") (pin "1") (pinfunction "1_1") (pintype "input"))
    )
    (net (code "22") (name "Net-(Q1-D)") (class "Default")
      (node (ref "P1") (pin "1") (pinfunction "1_1") (pintype "input"))
      (node (ref "Q1") (pin "3") (pinfunction "D_3") (pintype "unspecified"))
    )
    (net (code "23") (name "Net-(Q1-G)") (class "Default")
      (node (ref "Q1") (pin "1") (pinfunction "G_1") (pintype "unspecified"))
      (node (ref "R15") (pin "1") (pinfunction "1_1") (pintype "input"))
    )
    (net (code "24") (name "Net-(U1-IO40)") (class "Default")
      (node (ref "R5") (pin "2") (pinfunction "2_2") (pintype "input"))
      (node (ref "U1") (pin "36") (pinfunction "IO40_36") (pintype "unspecified"))
    )
    (net (code "25") (name "Net-(U1-IO45)") (class "Default")
      (node (ref "R4") (pin "1") (pinfunction "1_1") (pintype "unspecified"))
      (node (ref "U1") (pin "41") (pinfunction "IO45_41") (pintype "unspecified"))
    )
    (net (code "26") (name "Net-(U1-IO46)") (class "Default")
      (node (ref "R2") (pin "1") (pinfunction "1_1") (pintype "unspecified"))
      (node (ref "U1") (pin "44") (pinfunction "IO46_44") (pintype "unspecified"))
    )
    (net (code "27") (name "Net-(U2-PROG)") (class "Default")
      (node (ref "R8") (pin "1") (pinfunction "1_1") (pintype "input"))
      (node (ref "U2") (pin "5") (pinfunction "PROG_5") (pintype "unspecified"))
    )
    (net (code "28") (name "Net-(U3-BIAS)") (class "Default")
      (node (ref "C18") (pin "2") (pinfunction "2_2") (pintype "input"))
      (node (ref "U3") (pin "12") (pinfunction "BIAS_12") (pintype "unspecified"))
    )
    (net (code "29") (name "Net-(U3-CG)") (class "Default")
      (node (ref "C16") (pin "2") (pinfunction "2_2") (pintype "unspecified"))
      (node (ref "U3") (pin "3") (pinfunction "CG_3") (pintype "unspecified"))
    )
    (net (code "30") (name "Net-(U3-CT)") (class "Default")
      (node (ref "C17") (pin "2") (pinfunction "2_2") (pintype "input"))
      (node (ref "U3") (pin "1") (pinfunction "CT_1") (pintype "unspecified"))
    )
    (net (code "31") (name "Net-(U3-MICBIAS)") (class "Default")
      (node (ref "R10") (pin "1") (pinfunction "1_1") (pintype "input"))
      (node (ref "R9") (pin "2") (pinfunction "2_2") (pintype "input"))
      (node (ref "U3") (pin "13") (pinfunction "MICBIAS_13") (pintype "unspecified"))
    )
    (net (code "32") (name "Net-(U3-MICIN)") (class "Default")
      (node (ref "C19") (pin "2") (pinfunction "2_2") (pintype "unspecified"))
      (node (ref "U3") (pin "8") (pinfunction "MICIN_8") (pintype "unspecified"))
    )
    (net (code "33") (name "Net-(U3-TH)") (class "Default")
      (node (ref "R10") (pin "2") (pinfunction "2_2") (pintype "input"))
      (node (ref "R11") (pin "1") (pinfunction "1_1") (pintype "unspecified"))
      (node (ref "U3") (pin "14") (pinfunction "TH_14") (pintype "unspecified"))
    )
    (net (code "34") (name "Net-(U19-BIAS)") (class "Default")
      (node (ref "C24") (pin "2") (pinfunction "2_2") (pintype "input"))
      (node (ref "U19") (pin "12") (pinfunction "BIAS_12") (pintype "unspecified"))
    )
    (net (code "35") (name "Net-(U19-CG)") (class "Default")
      (node (ref "C21") (pin "2") (pinfunction "2_2") (pintype "unspecified"))
      (node (ref "U19") (pin "3") (pinfunction "CG_3") (pintype "unspecified"))
    )
    (net (code "36") (name "Net-(U19-CT)") (class "Default")
      (node (ref "C22") (pin "2") (pinfunction "2_2") (pintype "input"))
      (node (ref "U19") (pin "1") (pinfunction "CT_1") (pintype "unspecified"))
    )
    (net (code "37") (name "Net-(U19-MICBIAS)") (class "Default")
      (node (ref "R12") (pin "2") (pinfunction "2_2") (pintype "input"))
      (node (ref "R13") (pin "1") (pinfunction "1_1") (pintype "input"))
      (node (ref "U19") (pin "13") (pinfunction "MICBIAS_13") (pintype "unspecified"))
    )
    (net (code "38") (name "Net-(U19-MICIN)") (class "Default")
      (node (ref "C25") (pin "2") (pinfunction "2_2") (pintype "unspecified"))
      (node (ref "U19") (pin "8") (pinfunction "MICIN_8") (pintype "unspecified"))
    )
    (net (code "39") (name "Net-(U19-TH)") (class "Default")
      (node (ref "R13") (pin "2") (pinfunction "2_2") (pintype "input"))
      (node (ref "R14") (pin "1") (pinfunction "1_1") (pintype "unspecified"))
      (node (ref "U19") (pin "14") (pinfunction "TH_14") (pintype "unspecified"))
    )
    (net (code "40") (name "Net-(USB1-CC1)") (class "Default")
      (node (ref "R16") (pin "2") (pinfunction "2_2") (pintype "input"))
      (node (ref "USB1") (pin "4") (pinfunction "CC1_4") (pintype "unspecified"))
    )
    (net (code "41") (name "Net-(USB1-CC2)") (class "Default")
      (node (ref "R7") (pin "2") (pinfunction "2_2") (pintype "input"))
      (node (ref "USB1") (pin "10") (pinfunction "CC2_10") (pintype "unspecified"))
    )
    (net (code "42") (name "POWER_+3V3") (class "Default")
      (node (ref "C1") (pin "2") (pinfunction "2_2") (pintype "unspecified"))
      (node (ref "C10") (pin "2") (pinfunction "2_2") (pintype "unspecified"))
      (node (ref "C11") (pin "2") (pinfunction "2_2") (pintype "unspecified"))
      (node (ref "C14") (pin "1") (pinfunction "1_1") (pintype "unspecified"))
      (node (ref "C15") (pin "1") (pinfunction "1_1") (pintype "input"))
      (node (ref "C2") (pin "2") (pinfunction "2_2") (pintype "unspecified"))
      (node (ref "C20") (pin "1") (pinfunction "1_1") (pintype "unspecified"))
      (node (ref "C23") (pin "1") (pinfunction "1_1") (pintype "input"))
      (node (ref "CARD1") (pin "4") (pinfunction "VDD_4") (pintype "unspecified"))
      (node (ref "R1") (pin "1") (pinfunction "1_1") (pintype "unspecified"))
      (node (ref "R3") (pin "2") (pinfunction "2_2") (pintype "unspecified"))
      (node (ref "U1") (pin "3") (pinfunction "3V3_3") (pintype "unspecified"))
      (node (ref "U19") (pin "2") (pinfunction "SHDN#_2") (pintype "unspecified"))
      (node (ref "U19") (pin "5") (pinfunction "VDD_5") (pintype "unspecified"))
      (node (ref "U3") (pin "2") (pinfunction "SHDN#_2") (pintype "unspecified"))
      (node (ref "U3") (pin "5") (pinfunction "VDD_5") (pintype "unspecified"))
      (node (ref "U4") (pin "3") (pinfunction "VOUT_3") (pintype "input"))
    )
    (net (code "43") (name "POWER_VDC") (class "Default")
      (node (ref "C12") (pin "2") (pinfunction "2_2") (pintype "unspecified"))
      (node (ref "C8") (pin "2") (pinfunction "2_2") (pintype "unspecified"))
      (node (ref "C9") (pin "2") (pinfunction "2_2") (pintype "unspecified"))
      (node (ref "JP1") (pin "1") (pinfunction "1_1") (pintype "input"))
      (node (ref "P2") (pin "1") (pinfunction "1_1") (pintype "input"))
      (node (ref "P3") (pin "1") (pinfunction "1_1") (pintype "input"))
      (node (ref "U2") (pin "3") (pinfunction "VBAT_3") (pintype "unspecified"))
      (node (ref "U4") (pin "2") (pinfunction "VIN_2") (pintype "input"))
    )
    (net (code "44") (name "STAT") (class "Default")
      (node (ref "U1") (pin "15") (pinfunction "IO11_15") (pintype "unspecified"))
      (node (ref "U2") (pin "1") (pinfunction "STAT_1") (pintype "unspecified"))
    )
    (net (code "45") (name "unconnected-(CARD1-DAT1-Pad8)") (class "Default")
      (node (ref "CARD1") (pin "8") (pinfunction "DAT1_8") (pintype "unspecified+no_connect"))
    )
    (net (code "46") (name "unconnected-(CARD1-DAT2-Pad1)") (class "Default")
      (node (ref "CARD1") (pin "1") (pinfunction "DAT2_1") (pintype "unspecified+no_connect"))
    )
    (net (code "47") (name "unconnected-(U1-IO1-Pad5)") (class "Default")
      (node (ref "U1") (pin "5") (pinfunction "IO1_5") (pintype "unspecified+no_connect"))
    )
    (net (code "48") (name "unconnected-(U1-IO2-Pad6)") (class "Default")
      (node (ref "U1") (pin "6") (pinfunction "IO2_6") (pintype "unspecified+no_connect"))
    )
    (net (code "49") (name "unconnected-(U1-IO3-Pad7)") (class "Default")
      (node (ref "U1") (pin "7") (pinfunction "IO3_7") (pintype "unspecified+no_connect"))
    )
    (net (code "50") (name "unconnected-(U1-IO12-Pad16)") (class "Default")
      (node (ref "U1") (pin "16") (pinfunction "IO12_16") (pintype "unspecified+no_connect"))
    )
    (net (code "51") (name "unconnected-(U1-IO13-Pad17)") (class "Default")
      (node (ref "U1") (pin "17") (pinfunction "IO13_17") (pintype "unspecified+no_connect"))
    )
    (net (code "52") (name "unconnected-(U1-IO14-Pad18)") (class "Default")
      (node (ref "U1") (pin "18") (pinfunction "IO14_18") (pintype "unspecified+no_connect"))
    )
    (net (code "53") (name "unconnected-(U1-IO15-Pad19)") (class "Default")
      (node (ref "U1") (pin "19") (pinfunction "IO15_19") (pintype "unspecified+no_connect"))
    )
    (net (code "54") (name "unconnected-(U1-IO17-Pad21)") (class "Default")
      (node (ref "U1") (pin "21") (pinfunction "IO17_21") (pintype "unspecified+no_connect"))
    )
    (net (code "55") (name "unconnected-(U1-IO18-Pad22)") (class "Default")
      (node (ref "U1") (pin "22") (pinfunction "IO18_22") (pintype "unspecified+no_connect"))
    )
    (net (code "56") (name "unconnected-(U1-IO21-Pad25)") (class "Default")
      (node (ref "U1") (pin "25") (pinfunction "IO21_25") (pintype "unspecified+no_connect"))
    )
    (net (code "57") (name "unconnected-(U1-IO26-Pad26)") (class "Default")
      (node (ref "U1") (pin "26") (pinfunction "IO26_26") (pintype "unspecified+no_connect"))
    )
    (net (code "58") (name "unconnected-(U1-IO33-Pad28)") (class "Default")
      (node (ref "U1") (pin "28") (pinfunction "IO33_28") (pintype "unspecified+no_connect"))
    )
    (net (code "59") (name "unconnected-(U1-IO34-Pad29)") (class "Default")
      (node (ref "U1") (pin "29") (pinfunction "IO34_29") (pintype "unspecified+no_connect"))
    )
    (net (code "60") (name "unconnected-(U1-IO38-Pad34)") (class "Default")
      (node (ref "U1") (pin "34") (pinfunction "IO38_34") (pintype "unspecified+no_connect"))
    )
    (net (code "61") (name "unconnected-(U1-IO41-Pad37)") (class "Default")
      (node (ref "U1") (pin "37") (pinfunction "IO41_37") (pintype "unspecified+no_connect"))
    )
    (net (code "62") (name "unconnected-(U1-IO42-Pad38)") (class "Default")
      (node (ref "U1") (pin "38") (pinfunction "IO42_38") (pintype "unspecified+no_connect"))
    )
    (net (code "63") (name "unconnected-(U1-IO47-Pad27)") (class "Default")
      (node (ref "U1") (pin "27") (pinfunction "IO47_27") (pintype "unspecified+no_connect"))
    )
    (net (code "64") (name "unconnected-(U1-IO48-Pad30)") (class "Default")
      (node (ref "U1") (pin "30") (pinfunction "IO48_30") (pintype "unspecified+no_connect"))
    )
    (net (code "65") (name "unconnected-(U1-RXD0-Pad40)") (class "Default")
      (node (ref "U1") (pin "40") (pinfunction "RXD0_40") (pintype "unspecified+no_connect"))
    )
    (net (code "66") (name "unconnected-(U1-TXD0-Pad39)") (class "Default")
      (node (ref "U1") (pin "39") (pinfunction "TXD0_39") (pintype "unspecified+no_connect"))
    )
    (net (code "67") (name "unconnected-(USB1-SBU1-Pad9)") (class "Default")
      (node (ref "USB1") (pin "9") (pinfunction "SBU1_9") (pintype "unspecified+no_connect"))
    )
    (net (code "68") (name "unconnected-(USB1-SBU2-Pad3)") (class "Default")
      (node (ref "USB1") (pin "3") (pinfunction "SBU2_3") (pintype "unspecified+no_connect"))
    )
  )
)
